# FEU31_Part1.net
KiCad netlist of a schematic drawn in Altium Designer
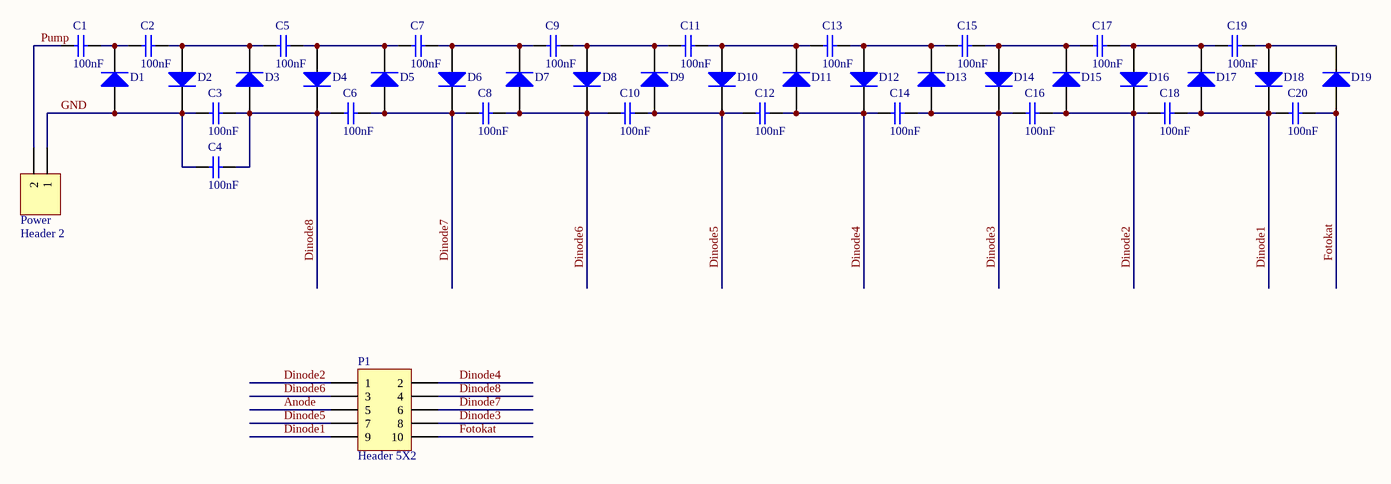
[diagram p0: FEU31_Part1.SchDoc]

(export (version "E")
  (design (tool "Eeschema 10.0.6"))
  (components
    (comp (ref "C1")
      (value "100nF")
      (footprint "Miscellaneous Devices:C1206")
      (description "Capacitor (Semiconductor SIM Model)")
      (fields (field (name "PUBLISHER") "Altium Limited"))
      (libsource (lib "Miscellaneous Devices") (part "Cap Semi"))
    )
    (comp (ref "C2")
      (value "100nF")
      (footprint "Miscellaneous Devices:C1206")
      (description "Capacitor (Semiconductor SIM Model)")
      (fields (field (name "PUBLISHER") "Altium Limited"))
      (libsource (lib "Miscellaneous Devices") (part "Cap Semi"))
    )
    (comp (ref "C3")
      (value "100nF")
      (footprint "Miscellaneous Devices:C1206")
      (description "Capacitor (Semiconductor SIM Model)")
      (fields (field (name "PUBLISHER") "Altium Limited"))
      (libsource (lib "Miscellaneous Devices") (part "Cap Semi"))
    )
    (comp (ref "C4")
      (value "100nF")
      (footprint "Miscellaneous Devices:C1206")
      (description "Capacitor (Semiconductor SIM Model)")
      (fields (field (name "PUBLISHER") "Altium Limited"))
      (libsource (lib "Miscellaneous Devices") (part "Cap Semi"))
    )
    (comp (ref "C5")
      (value "100nF")
      (footprint "Miscellaneous Devices:C1206")
      (description "Capacitor (Semiconductor SIM Model)")
      (fields (field (name "PUBLISHER") "Altium Limited"))
      (libsource (lib "Miscellaneous Devices") (part "Cap Semi"))
    )
    (comp (ref "C6")
      (value "100nF")
      (footprint "Miscellaneous Devices:C1206")
      (description "Capacitor (Semiconductor SIM Model)")
      (fields (field (name "PUBLISHER") "Altium Limited"))
      (libsource (lib "Miscellaneous Devices") (part "Cap Semi"))
    )
    (comp (ref "C7")
      (value "100nF")
      (footprint "Miscellaneous Devices:C1206")
      (description "Capacitor (Semiconductor SIM Model)")
      (fields (field (name "PUBLISHER") "Altium Limited"))
      (libsource (lib "Miscellaneous Devices") (part "Cap Semi"))
    )
    (comp (ref "C8")
      (value "100nF")
      (footprint "Miscellaneous Devices:C1206")
      (description "Capacitor (Semiconductor SIM Model)")
      (fields (field (name "PUBLISHER") "Altium Limited"))
      (libsource (lib "Miscellaneous Devices") (part "Cap Semi"))
    )
    (comp (ref "C9")
      (value "100nF")
      (footprint "Miscellaneous Devices:C1206")
      (description "Capacitor (Semiconductor SIM Model)")
      (fields (field (name "PUBLISHER") "Altium Limited"))
      (libsource (lib "Miscellaneous Devices") (part "Cap Semi"))
    )
    (comp (ref "C10")
      (value "100nF")
      (footprint "Miscellaneous Devices:C1206")
      (description "Capacitor (Semiconductor SIM Model)")
      (fields (field (name "PUBLISHER") "Altium Limited"))
      (libsource (lib "Miscellaneous Devices") (part "Cap Semi"))
    )
    (comp (ref "C11")
      (value "100nF")
      (footprint "Miscellaneous Devices:C1206")
      (description "Capacitor (Semiconductor SIM Model)")
      (fields (field (name "PUBLISHER") "Altium Limited"))
      (libsource (lib "Miscellaneous Devices") (part "Cap Semi"))
    )
    (comp (ref "C12")
      (value "100nF")
      (footprint "Miscellaneous Devices:C1206")
      (description "Capacitor (Semiconductor SIM Model)")
      (fields (field (name "PUBLISHER") "Altium Limited"))
      (libsource (lib "Miscellaneous Devices") (part "Cap Semi"))
    )
    (comp (ref "C13")
      (value "100nF")
      (footprint "Miscellaneous Devices:C1206")
      (description "Capacitor (Semiconductor SIM Model)")
      (fields (field (name "PUBLISHER") "Altium Limited"))
      (libsource (lib "Miscellaneous Devices") (part "Cap Semi"))
    )
    (comp (ref "C14")
      (value "100nF")
      (footprint "Miscellaneous Devices:C1206")
      (description "Capacitor (Semiconductor SIM Model)")
      (fields (field (name "PUBLISHER") "Altium Limited"))
      (libsource (lib "Miscellaneous Devices") (part "Cap Semi"))
    )
    (comp (ref "C15")
      (value "100nF")
      (footprint "Miscellaneous Devices:C1206")
      (description "Capacitor (Semiconductor SIM Model)")
      (fields (field (name "PUBLISHER") "Altium Limited"))
      (libsource (lib "Miscellaneous Devices") (part "Cap Semi"))
    )
    (comp (ref "C16")
      (value "100nF")
      (footprint "Miscellaneous Devices:C1206")
      (description "Capacitor (Semiconductor SIM Model)")
      (fields (field (name "PUBLISHER") "Altium Limited"))
      (libsource (lib "Miscellaneous Devices") (part "Cap Semi"))
    )
    (comp (ref "C17")
      (value "100nF")
      (footprint "Miscellaneous Devices:C1206")
      (description "Capacitor (Semiconductor SIM Model)")
      (fields (field (name "PUBLISHER") "Altium Limited"))
      (libsource (lib "Miscellaneous Devices") (part "Cap Semi"))
    )
    (comp (ref "C18")
      (value "100nF")
      (footprint "Miscellaneous Devices:C1206")
      (description "Capacitor (Semiconductor SIM Model)")
      (fields (field (name "PUBLISHER") "Altium Limited"))
      (libsource (lib "Miscellaneous Devices") (part "Cap Semi"))
    )
    (comp (ref "C19")
      (value "100nF")
      (footprint "Miscellaneous Devices:C1206")
      (description "Capacitor (Semiconductor SIM Model)")
      (fields (field (name "PUBLISHER") "Altium Limited"))
      (libsource (lib "Miscellaneous Devices") (part "Cap Semi"))
    )
    (comp (ref "C20")
      (value "100nF")
      (footprint "Miscellaneous Devices:C1206")
      (description "Capacitor (Semiconductor SIM Model)")
      (fields (field (name "PUBLISHER") "Altium Limited"))
      (libsource (lib "Miscellaneous Devices") (part "Cap Semi"))
    )
    (comp (ref "D1")
      (value "~")
      (footprint "DA2JF8100L")
      (description "Default Diode")
      (fields (field (name "PUBLISHER") "Altium Limited"))
      (libsource (lib "Miscellaneous Devices") (part "Diode"))
    )
    (comp (ref "D2")
      (value "~")
      (footprint "DA2JF8100L")
      (description "Default Diode")
      (fields (field (name "PUBLISHER") "Altium Limited"))
      (libsource (lib "Miscellaneous Devices") (part "Diode"))
    )
    (comp (ref "D3")
      (value "~")
      (footprint "DA2JF8100L")
      (description "Default Diode")
      (fields (field (name "PUBLISHER") "Altium Limited"))
      (libsource (lib "Miscellaneous Devices") (part "Diode"))
    )
    (comp (ref "D4")
      (value "~")
      (footprint "DA2JF8100L")
      (description "Default Diode")
      (fields (field (name "PUBLISHER") "Altium Limited"))
      (libsource (lib "Miscellaneous Devices") (part "Diode"))
    )
    (comp (ref "D5")
      (value "~")
      (footprint "DA2JF8100L")
      (description "Default Diode")
      (fields (field (name "PUBLISHER") "Altium Limited"))
      (libsource (lib "Miscellaneous Devices") (part "Diode"))
    )
    (comp (ref "D6")
      (value "~")
      (footprint "DA2JF8100L")
      (description "Default Diode")
      (fields (field (name "PUBLISHER") "Altium Limited"))
      (libsource (lib "Miscellaneous Devices") (part "Diode"))
    )
    (comp (ref "D7")
      (value "~")
      (footprint "DA2JF8100L")
      (description "Default Diode")
      (fields (field (name "PUBLISHER") "Altium Limited"))
      (libsource (lib "Miscellaneous Devices") (part "Diode"))
    )
    (comp (ref "D8")
      (value "~")
      (footprint "DA2JF8100L")
      (description "Default Diode")
      (fields (field (name "PUBLISHER") "Altium Limited"))
      (libsource (lib "Miscellaneous Devices") (part "Diode"))
    )
    (comp (ref "D9")
      (value "~")
      (footprint "DA2JF8100L")
      (description "Default Diode")
      (fields (field (name "PUBLISHER") "Altium Limited"))
      (libsource (lib "Miscellaneous Devices") (part "Diode"))
    )
    (comp (ref "D10")
      (value "~")
      (footprint "DA2JF8100L")
      (description "Default Diode")
      (fields (field (name "PUBLISHER") "Altium Limited"))
      (libsource (lib "Miscellaneous Devices") (part "Diode"))
    )
    (comp (ref "D11")
      (value "~")
      (footprint "DA2JF8100L")
      (description "Default Diode")
      (fields (field (name "PUBLISHER") "Altium Limited"))
      (libsource (lib "Miscellaneous Devices") (part "Diode"))
    )
    (comp (ref "D12")
      (value "~")
      (footprint "DA2JF8100L")
      (description "Default Diode")
      (fields (field (name "PUBLISHER") "Altium Limited"))
      (libsource (lib "Miscellaneous Devices") (part "Diode"))
    )
    (comp (ref "D13")
      (value "~")
      (footprint "DA2JF8100L")
      (description "Default Diode")
      (fields (field (name "PUBLISHER") "Altium Limited"))
      (libsource (lib "Miscellaneous Devices") (part "Diode"))
    )
    (comp (ref "D14")
      (value "~")
      (footprint "DA2JF8100L")
      (description "Default Diode")
      (fields (field (name "PUBLISHER") "Altium Limited"))
      (libsource (lib "Miscellaneous Devices") (part "Diode"))
    )
    (comp (ref "D15")
      (value "~")
      (footprint "DA2JF8100L")
      (description "Default Diode")
      (fields (field (name "PUBLISHER") "Altium Limited"))
      (libsource (lib "Miscellaneous Devices") (part "Diode"))
    )
    (comp (ref "D16")
      (value "~")
      (footprint "DA2JF8100L")
      (description "Default Diode")
      (fields (field (name "PUBLISHER") "Altium Limited"))
      (libsource (lib "Miscellaneous Devices") (part "Diode"))
    )
    (comp (ref "D17")
      (value "~")
      (footprint "DA2JF8100L")
      (description "Default Diode")
      (fields (field (name "PUBLISHER") "Altium Limited"))
      (libsource (lib "Miscellaneous Devices") (part "Diode"))
    )
    (comp (ref "D18")
      (value "~")
      (footprint "DA2JF8100L")
      (description "Default Diode")
      (fields (field (name "PUBLISHER") "Altium Limited"))
      (libsource (lib "Miscellaneous Devices") (part "Diode"))
    )
    (comp (ref "D19")
      (value "~")
      (footprint "DA2JF8100L")
      (description "Default Diode")
      (fields (field (name "PUBLISHER") "Altium Limited"))
      (libsource (lib "Miscellaneous Devices") (part "Diode"))
    )
    (comp (ref "P1")
      (value "Header 5X2")
      (footprint "ФЭУ-31")
      (description "Header, 5-Pin, Dual row")
      (fields (field (name "PUBLISHER") "Altium Limited"))
      (libsource (lib "Miscellaneous Connectors") (part "Header 5X2"))
    )
    (comp (ref "Power")
      (value "Header 2")
      (footprint "HDR1X2")
      (description "Header, 2-Pin")
      (fields (field (name "PUBLISHER") "Altium Limited"))
      (libsource (lib "Miscellaneous Connectors") (part "Header 2"))
    )
  )
  (nets
    (net (code "1") (name "/Anode") (class "Default")
      (node (ref "P1") (pin "5") (pinfunction "5_5") (pintype "passive"))
    )
    (net (code "2") (name "/Dinode1") (class "Default")
      (node (ref "C18") (pin "1") (pinfunction "1_1") (pintype "passive"))
      (node (ref "C20") (pin "2") (pinfunction "2_2") (pintype "passive"))
      (node (ref "D17") (pin "1") (pinfunction "A_1") (pintype "passive"))
      (node (ref "D18") (pin "2") (pinfunction "K_2") (pintype "passive"))
      (node (ref "P1") (pin "9") (pinfunction "9_9") (pintype "passive"))
    )
    (net (code "3") (name "/Dinode2") (class "Default")
      (node (ref "C16") (pin "1") (pinfunction "1_1") (pintype "passive"))
      (node (ref "C18") (pin "2") (pinfunction "2_2") (pintype "passive"))
      (node (ref "D15") (pin "1") (pinfunction "A_1") (pintype "passive"))
      (node (ref "D16") (pin "2") (pinfunction "K_2") (pintype "passive"))
      (node (ref "P1") (pin "1") (pinfunction "1_1") (pintype "passive"))
    )
    (net (code "4") (name "/Dinode3") (class "Default")
      (node (ref "C14") (pin "1") (pinfunction "1_1") (pintype "passive"))
      (node (ref "C16") (pin "2") (pinfunction "2_2") (pintype "passive"))
      (node (ref "D13") (pin "1") (pinfunction "A_1") (pintype "passive"))
      (node (ref "D14") (pin "2") (pinfunction "K_2") (pintype "passive"))
      (node (ref "P1") (pin "8") (pinfunction "8_8") (pintype "passive"))
    )
    (net (code "5") (name "/Dinode4") (class "Default")
      (node (ref "C12") (pin "1") (pinfunction "1_1") (pintype "passive"))
      (node (ref "C14") (pin "2") (pinfunction "2_2") (pintype "passive"))
      (node (ref "D11") (pin "1") (pinfunction "A_1") (pintype "passive"))
      (node (ref "D12") (pin "2") (pinfunction "K_2") (pintype "passive"))
      (node (ref "P1") (pin "2") (pinfunction "2_2") (pintype "passive"))
    )
    (net (code "6") (name "/Dinode5") (class "Default")
      (node (ref "C10") (pin "1") (pinfunction "1_1") (pintype "passive"))
      (node (ref "C12") (pin "2") (pinfunction "2_2") (pintype "passive"))
      (node (ref "D10") (pin "2") (pinfunction "K_2") (pintype "passive"))
      (node (ref "D9") (pin "1") (pinfunction "A_1") (pintype "passive"))
      (node (ref "P1") (pin "7") (pinfunction "7_7") (pintype "passive"))
    )
    (net (code "7") (name "/Dinode6") (class "Default")
      (node (ref "C10") (pin "2") (pinfunction "2_2") (pintype "passive"))
      (node (ref "C8") (pin "1") (pinfunction "1_1") (pintype "passive"))
      (node (ref "D7") (pin "1") (pinfunction "A_1") (pintype "passive"))
      (node (ref "D8") (pin "2") (pinfunction "K_2") (pintype "passive"))
      (node (ref "P1") (pin "3") (pinfunction "3_3") (pintype "passive"))
    )
    (net (code "8") (name "/Dinode7") (class "Default")
      (node (ref "C6") (pin "1") (pinfunction "1_1") (pintype "passive"))
      (node (ref "C8") (pin "2") (pinfunction "2_2") (pintype "passive"))
      (node (ref "D5") (pin "1") (pinfunction "A_1") (pintype "passive"))
      (node (ref "D6") (pin "2") (pinfunction "K_2") (pintype "passive"))
      (node (ref "P1") (pin "6") (pinfunction "6_6") (pintype "passive"))
    )
    (net (code "9") (name "/Dinode8") (class "Default")
      (node (ref "C3") (pin "1") (pinfunction "1_1") (pintype "passive"))
      (node (ref "C4") (pin "1") (pinfunction "1_1") (pintype "passive"))
      (node (ref "C6") (pin "2") (pinfunction "2_2") (pintype "passive"))
      (node (ref "D3") (pin "1") (pinfunction "A_1") (pintype "passive"))
      (node (ref "D4") (pin "2") (pinfunction "K_2") (pintype "passive"))
      (node (ref "P1") (pin "4") (pinfunction "4_4") (pintype "passive"))
    )
    (net (code "10") (name "/Fotokat") (class "Default")
      (node (ref "C20") (pin "1") (pinfunction "1_1") (pintype "passive"))
      (node (ref "D19") (pin "1") (pinfunction "A_1") (pintype "passive"))
      (node (ref "P1") (pin "10") (pinfunction "10_10") (pintype "passive"))
    )
    (net (code "11") (name "/GND") (class "Default")
      (node (ref "C3") (pin "2") (pinfunction "2_2") (pintype "passive"))
      (node (ref "C4") (pin "2") (pinfunction "2_2") (pintype "passive"))
      (node (ref "D1") (pin "1") (pinfunction "A_1") (pintype "passive"))
      (node (ref "D2") (pin "2") (pinfunction "K_2") (pintype "passive"))
      (node (ref "Power") (pin "1") (pinfunction "1_1") (pintype "passive"))
    )
    (net (code "12") (name "/Pump") (class "Default")
      (node (ref "C1") (pin "2") (pinfunction "2_2") (pintype "passive"))
      (node (ref "Power") (pin "2") (pinfunction "2_2") (pintype "passive"))
    )
    (net (code "13") (name "Net-(D1-K)") (class "Default")
      (node (ref "C1") (pin "1") (pinfunction "1_1") (pintype "passive"))
      (node (ref "C2") (pin "2") (pinfunction "2_2") (pintype "passive"))
      (node (ref "D1") (pin "2") (pinfunction "K_2") (pintype "passive"))
    )
    (net (code "14") (name "Net-(D2-A)") (class "Default")
      (node (ref "C2") (pin "1") (pinfunction "1_1") (pintype "passive"))
      (node (ref "C5") (pin "2") (pinfunction "2_2") (pintype "passive"))
      (node (ref "D2") (pin "1") (pinfunction "A_1") (pintype "passive"))
      (node (ref "D3") (pin "2") (pinfunction "K_2") (pintype "passive"))
    )
    (net (code "15") (name "Net-(D4-A)") (class "Default")
      (node (ref "C5") (pin "1") (pinfunction "1_1") (pintype "passive"))
      (node (ref "C7") (pin "2") (pinfunction "2_2") (pintype "passive"))
      (node (ref "D4") (pin "1") (pinfunction "A_1") (pintype "passive"))
      (node (ref "D5") (pin "2") (pinfunction "K_2") (pintype "passive"))
    )
    (net (code "16") (name "Net-(D6-A)") (class "Default")
      (node (ref "C7") (pin "1") (pinfunction "1_1") (pintype "passive"))
      (node (ref "C9") (pin "2") (pinfunction "2_2") (pintype "passive"))
      (node (ref "D6") (pin "1") (pinfunction "A_1") (pintype "passive"))
      (node (ref "D7") (pin "2") (pinfunction "K_2") (pintype "passive"))
    )
    (net (code "17") (name "Net-(D8-A)") (class "Default")
      (node (ref "C11") (pin "2") (pinfunction "2_2") (pintype "passive"))
      (node (ref "C9") (pin "1") (pinfunction "1_1") (pintype "passive"))
      (node (ref "D8") (pin "1") (pinfunction "A_1") (pintype "passive"))
      (node (ref "D9") (pin "2") (pinfunction "K_2") (pintype "passive"))
    )
    (net (code "18") (name "Net-(D10-A)") (class "Default")
      (node (ref "C11") (pin "1") (pinfunction "1_1") (pintype "passive"))
      (node (ref "C13") (pin "2") (pinfunction "2_2") (pintype "passive"))
      (node (ref "D10") (pin "1") (pinfunction "A_1") (pintype "passive"))
      (node (ref "D11") (pin "2") (pinfunction "K_2") (pintype "passive"))
    )
    (net (code "19") (name "Net-(D12-A)") (class "Default")
      (node (ref "C13") (pin "1") (pinfunction "1_1") (pintype "passive"))
      (node (ref "C15") (pin "2") (pinfunction "2_2") (pintype "passive"))
      (node (ref "D12") (pin "1") (pinfunction "A_1") (pintype "passive"))
      (node (ref "D13") (pin "2") (pinfunction "K_2") (pintype "passive"))
    )
    (net (code "20") (name "Net-(D14-A)") (class "Default")
      (node (ref "C15") (pin "1") (pinfunction "1_1") (pintype "passive"))
      (node (ref "C17") (pin "2") (pinfunction "2_2") (pintype "passive"))
      (node (ref "D14") (pin "1") (pinfunction "A_1") (pintype "passive"))
      (node (ref "D15") (pin "2") (pinfunction "K_2") (pintype "passive"))
    )
    (net (code "21") (name "Net-(D16-A)") (class "Default")
      (node (ref "C17") (pin "1") (pinfunction "1_1") (pintype "passive"))
      (node (ref "C19") (pin "2") (pinfunction "2_2") (pintype "passive"))
      (node (ref "D16") (pin "1") (pinfunction "A_1") (pintype "passive"))
      (node (ref "D17") (pin "2") (pinfunction "K_2") (pintype "passive"))
    )
    (net (code "22") (name "Net-(D18-A)") (class "Default")
      (node (ref "C19") (pin "1") (pinfunction "1_1") (pintype "passive"))
      (node (ref "D18") (pin "1") (pinfunction "A_1") (pintype "passive"))
      (node (ref "D19") (pin "2") (pinfunction "K_2") (pintype "passive"))
    )
  )
)
